# untitled.net
KiCad netlist of a schematic drawn in EAGLE
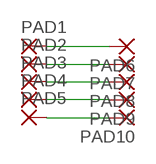
[diagram p0: schematic, sheet 1]

(export (version "E")
  (design (tool "Eeschema 10.0.6"))
  (components
    (comp (ref "PAD1")
      (value "2,15/1,0")
      (footprint "eagle-import:2,15_1,0")
      (libsource (lib "eagle-import") (part "2,15/1,0"))
    )
    (comp (ref "PAD2")
      (value "2,15/1,0")
      (footprint "eagle-import:2,15_1,0")
      (libsource (lib "eagle-import") (part "2,15/1,0"))
    )
    (comp (ref "PAD3")
      (value "2,15/1,0")
      (footprint "eagle-import:2,15_1,0")
      (libsource (lib "eagle-import") (part "2,15/1,0"))
    )
    (comp (ref "PAD4")
      (value "2,15/1,0")
      (footprint "eagle-import:2,15_1,0")
      (libsource (lib "eagle-import") (part "2,15/1,0"))
    )
    (comp (ref "PAD5")
      (value "2,15/1,0")
      (footprint "eagle-import:2,15_1,0")
      (libsource (lib "eagle-import") (part "2,15/1,0"))
    )
    (comp (ref "PAD6")
      (value "2,15/1,0")
      (footprint "eagle-import:2,15_1,0")
      (libsource (lib "eagle-import") (part "2,15/1,0"))
    )
    (comp (ref "PAD7")
      (value "2,15/1,0")
      (footprint "eagle-import:2,15_1,0")
      (libsource (lib "eagle-import") (part "2,15/1,0"))
    )
    (comp (ref "PAD8")
      (value "2,15/1,0")
      (footprint "eagle-import:2,15_1,0")
      (libsource (lib "eagle-import") (part "2,15/1,0"))
    )
    (comp (ref "PAD9")
      (value "2,15/1,0")
      (footprint "eagle-import:2,15_1,0")
      (libsource (lib "eagle-import") (part "2,15/1,0"))
    )
    (comp (ref "PAD10")
      (value "2,15/1,0")
      (footprint "eagle-import:2,15_1,0")
      (libsource (lib "eagle-import") (part "2,15/1,0"))
    )
  )
  (nets
    (net (code "1") (name "Net-(PAD1-P)") (class "Default")
      (node (ref "PAD1") (pin "1") (pinfunction "P_1") (pintype "passive"))
      (node (ref "PAD6") (pin "1") (pinfunction "P_1") (pintype "passive"))
    )
    (net (code "2") (name "Net-(PAD2-P)") (class "Default")
      (node (ref "PAD2") (pin "1") (pinfunction "P_1") (pintype "passive"))
      (node (ref "PAD7") (pin "1") (pinfunction "P_1") (pintype "passive"))
    )
    (net (code "3") (name "Net-(PAD3-P)") (class "Default")
      (node (ref "PAD3") (pin "1") (pinfunction "P_1") (pintype "passive"))
      (node (ref "PAD8") (pin "1") (pinfunction "P_1") (pintype "passive"))
    )
    (net (code "4") (name "Net-(PAD4-P)") (class "Default")
      (node (ref "PAD4") (pin "1") (pinfunction "P_1") (pintype "passive"))
      (node (ref "PAD9") (pin "1") (pinfunction "P_1") (pintype "passive"))
    )
    (net (code "5") (name "Net-(PAD10-P)") (class "Default")
      (node (ref "PAD10") (pin "1") (pinfunction "P_1") (pintype "passive"))
      (node (ref "PAD5") (pin "1") (pinfunction "P_1") (pintype "passive"))
    )
  )
)
